# motorControllerMk3.net
KiCad netlist of a schematic drawn in EAGLE
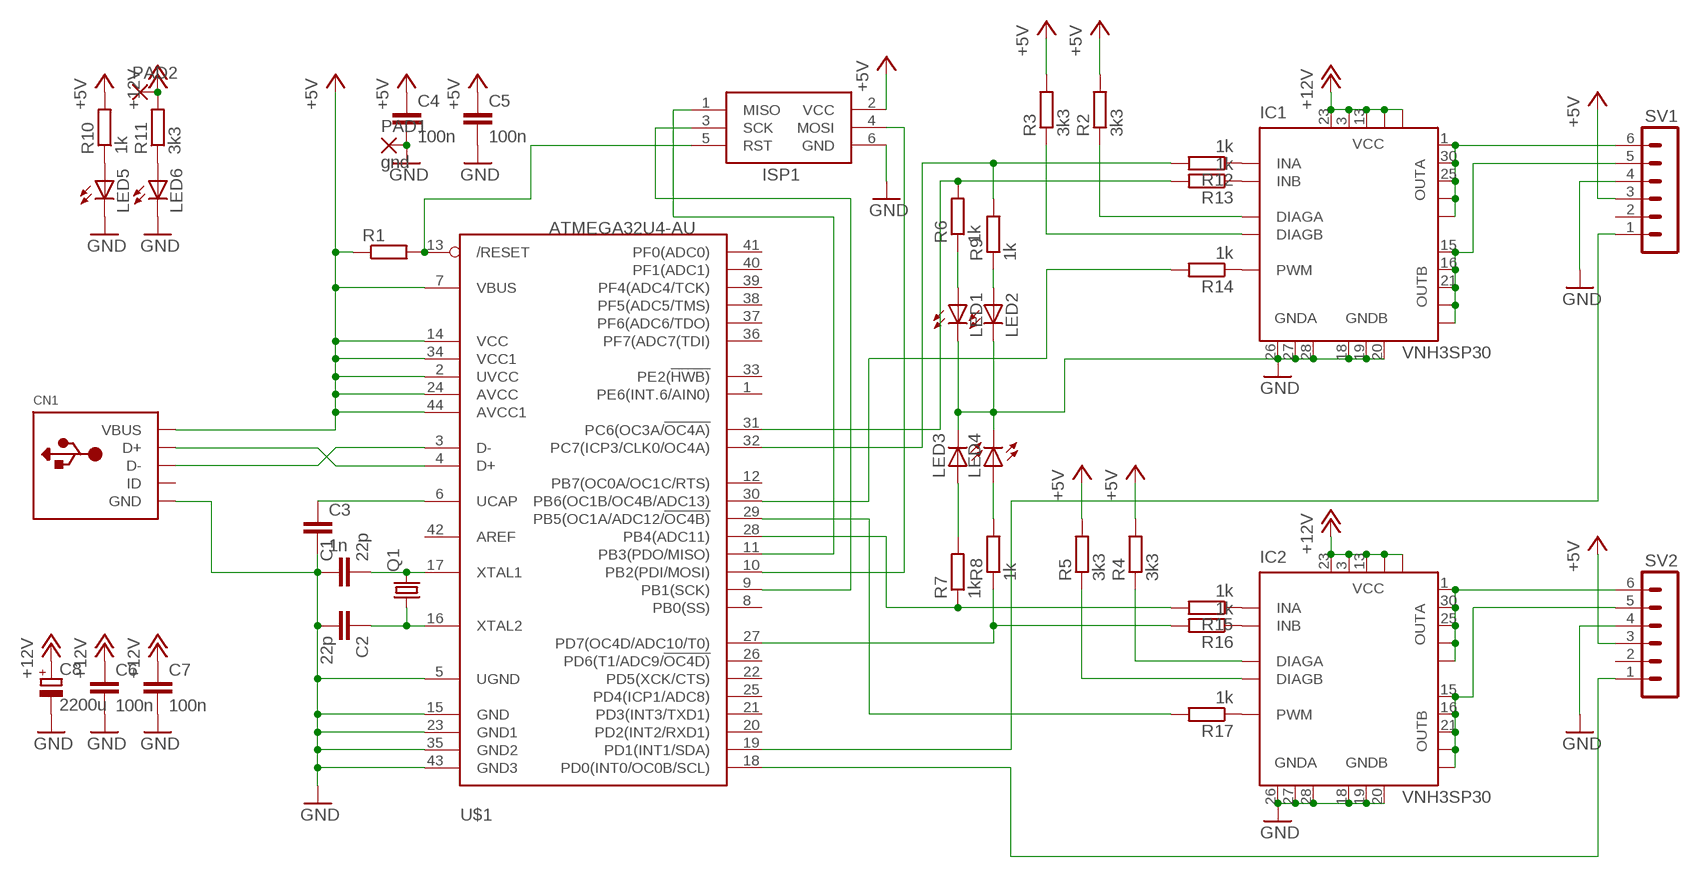
[diagram p0: schematic, sheet 1]

(export (version "E")
  (design (tool "Eeschema 10.0.6"))
  (components
    (comp (ref "C1")
      (value "22p")
      (footprint "eagle-import:C0805K")
      (libsource (lib "eagle-import") (part "C-EUC0805K"))
    )
    (comp (ref "C2")
      (value "22p")
      (footprint "eagle-import:C0805K")
      (libsource (lib "eagle-import") (part "C-EUC0805K"))
    )
    (comp (ref "C3")
      (value "1n")
      (footprint "eagle-import:C0805K")
      (libsource (lib "eagle-import") (part "C-EUC0805K"))
    )
    (comp (ref "C4")
      (value "100n")
      (footprint "eagle-import:C0805K")
      (libsource (lib "eagle-import") (part "C-EUC0805K"))
    )
    (comp (ref "C5")
      (value "100n")
      (footprint "eagle-import:C0805K")
      (libsource (lib "eagle-import") (part "C-EUC0805K"))
    )
    (comp (ref "C6")
      (value "100n")
      (footprint "eagle-import:C0805K")
      (libsource (lib "eagle-import") (part "C-EUC0805K"))
    )
    (comp (ref "C7")
      (value "100n")
      (footprint "eagle-import:C0805K")
      (libsource (lib "eagle-import") (part "C-EUC0805K"))
    )
    (comp (ref "C8")
      (value "2200u")
      (footprint "eagle-import:E5-8,5")
      (libsource (lib "eagle-import") (part "CPOL-EUE5-8.5"))
    )
    (comp (ref "CN1")
      (value "USBMINIB")
      (footprint "eagle-import:USB-MINIB")
      (libsource (lib "eagle-import") (part "USBMINIB"))
    )
    (comp (ref "IC1")
      (value "VNH3SP30")
      (footprint "eagle-import:MULTIPOWERSO-30")
      (fields (field (name "MPN") "VNH3SP30-E"))
      (libsource (lib "eagle-import") (part "VNH3SP30"))
    )
    (comp (ref "IC2")
      (value "VNH3SP30")
      (footprint "eagle-import:MULTIPOWERSO-30")
      (fields (field (name "MPN") "VNH3SP30-E"))
      (libsource (lib "eagle-import") (part "VNH3SP30"))
    )
    (comp (ref "ISP1")
      (value "AVRISP-6")
      (footprint "eagle-import:AVRISP")
      (libsource (lib "eagle-import") (part "AVRISP-6"))
    )
    (comp (ref "LED1")
      (value "LEDSML1206")
      (footprint "eagle-import:SML1206")
      (libsource (lib "eagle-import") (part "LEDSML1206"))
    )
    (comp (ref "LED2")
      (value "LEDSML1206")
      (footprint "eagle-import:SML1206")
      (libsource (lib "eagle-import") (part "LEDSML1206"))
    )
    (comp (ref "LED3")
      (value "LEDSML1206")
      (footprint "eagle-import:SML1206")
      (libsource (lib "eagle-import") (part "LEDSML1206"))
    )
    (comp (ref "LED4")
      (value "LEDSML1206")
      (footprint "eagle-import:SML1206")
      (libsource (lib "eagle-import") (part "LEDSML1206"))
    )
    (comp (ref "LED5")
      (value "LEDSML1206")
      (footprint "eagle-import:SML1206")
      (libsource (lib "eagle-import") (part "LEDSML1206"))
    )
    (comp (ref "LED6")
      (value "LEDSML1206")
      (footprint "eagle-import:SML1206")
      (libsource (lib "eagle-import") (part "LEDSML1206"))
    )
    (comp (ref "PAD1")
      (value "gnd")
      (footprint "eagle-import:3,81_1,1")
      (libsource (lib "eagle-import") (part "3,81/1,1"))
    )
    (comp (ref "PAD2")
      (value "3,81/1,1")
      (footprint "eagle-import:3,81_1,1")
      (libsource (lib "eagle-import") (part "3,81/1,1"))
    )
    (comp (ref "Q1")
      (value "CRYSTALHC49U-V")
      (footprint "eagle-import:HC49U-V")
      (libsource (lib "eagle-import") (part "CRYSTALHC49U-V"))
    )
    (comp (ref "R1")
      (value "R-EU_M0805")
      (footprint "eagle-import:M0805")
      (libsource (lib "eagle-import") (part "R-EU_M0805"))
    )
    (comp (ref "R2")
      (value "3k3")
      (footprint "eagle-import:M0805")
      (libsource (lib "eagle-import") (part "R-EU_M0805"))
    )
    (comp (ref "R3")
      (value "3k3")
      (footprint "eagle-import:M0805")
      (libsource (lib "eagle-import") (part "R-EU_M0805"))
    )
    (comp (ref "R4")
      (value "3k3")
      (footprint "eagle-import:M0805")
      (libsource (lib "eagle-import") (part "R-EU_M0805"))
    )
    (comp (ref "R5")
      (value "3k3")
      (footprint "eagle-import:M0805")
      (libsource (lib "eagle-import") (part "R-EU_M0805"))
    )
    (comp (ref "R6")
      (value "1k")
      (footprint "eagle-import:M0805")
      (libsource (lib "eagle-import") (part "R-EU_M0805"))
    )
    (comp (ref "R7")
      (value "1k")
      (footprint "eagle-import:M0805")
      (libsource (lib "eagle-import") (part "R-EU_M0805"))
    )
    (comp (ref "R8")
      (value "1k")
      (footprint "eagle-import:M0805")
      (libsource (lib "eagle-import") (part "R-EU_M0805"))
    )
    (comp (ref "R9")
      (value "1k")
      (footprint "eagle-import:M0805")
      (libsource (lib "eagle-import") (part "R-EU_M0805"))
    )
    (comp (ref "R10")
      (value "1k")
      (footprint "eagle-import:M0805")
      (libsource (lib "eagle-import") (part "R-EU_M0805"))
    )
    (comp (ref "R11")
      (value "3k3")
      (footprint "eagle-import:M0805")
      (libsource (lib "eagle-import") (part "R-EU_M0805"))
    )
    (comp (ref "R12")
      (value "1k")
      (footprint "eagle-import:M0805")
      (libsource (lib "eagle-import") (part "R-EU_M0805"))
    )
    (comp (ref "R13")
      (value "1k")
      (footprint "eagle-import:M0805")
      (libsource (lib "eagle-import") (part "R-EU_M0805"))
    )
    (comp (ref "R14")
      (value "1k")
      (footprint "eagle-import:M0805")
      (libsource (lib "eagle-import") (part "R-EU_M0805"))
    )
    (comp (ref "R15")
      (value "1k")
      (footprint "eagle-import:M0805")
      (libsource (lib "eagle-import") (part "R-EU_M0805"))
    )
    (comp (ref "R16")
      (value "1k")
      (footprint "eagle-import:M0805")
      (libsource (lib "eagle-import") (part "R-EU_M0805"))
    )
    (comp (ref "R17")
      (value "1k")
      (footprint "eagle-import:M0805")
      (libsource (lib "eagle-import") (part "R-EU_M0805"))
    )
    (comp (ref "SV1")
      (value "MA06-1")
      (footprint "eagle-import:MA06-1")
      (libsource (lib "eagle-import") (part "MA06-1"))
    )
    (comp (ref "SV2")
      (value "MA06-1")
      (footprint "eagle-import:MA06-1")
      (libsource (lib "eagle-import") (part "MA06-1"))
    )
    (comp (ref "U$1")
      (value "ATMEGA32U4-AU")
      (footprint "eagle-import:TQFP44")
      (libsource (lib "eagle-import") (part "ATMEGA32U4-AU"))
    )
  )
  (nets
    (net (code "1") (name "+5V") (class "Default")
      (node (ref "C4") (pin "1") (pinfunction "1_1") (pintype "passive"))
      (node (ref "C5") (pin "1") (pinfunction "1_1") (pintype "passive"))
      (node (ref "CN1") (pin "VBUS") (pinfunction "VBUS_VBUS") (pintype "power_in"))
      (node (ref "ISP1") (pin "2") (pinfunction "VCC_2") (pintype "power_in"))
      (node (ref "R1") (pin "1") (pinfunction "1_1") (pintype "passive"))
      (node (ref "R10") (pin "2") (pinfunction "2_2") (pintype "passive"))
      (node (ref "R2") (pin "2") (pinfunction "2_2") (pintype "passive"))
      (node (ref "R3") (pin "2") (pinfunction "2_2") (pintype "passive"))
      (node (ref "R4") (pin "2") (pinfunction "2_2") (pintype "passive"))
      (node (ref "R5") (pin "2") (pinfunction "2_2") (pintype "passive"))
      (node (ref "SV1") (pin "3") (pinfunction "3_3") (pintype "passive"))
      (node (ref "SV2") (pin "3") (pinfunction "3_3") (pintype "passive"))
      (node (ref "U$1") (pin "14") (pinfunction "VCC_14") (pintype "bidirectional"))
      (node (ref "U$1") (pin "2") (pinfunction "UVCC_2") (pintype "bidirectional"))
      (node (ref "U$1") (pin "24") (pinfunction "AVCC_24") (pintype "bidirectional"))
      (node (ref "U$1") (pin "34") (pinfunction "VCC1_34") (pintype "bidirectional"))
      (node (ref "U$1") (pin "44") (pinfunction "AVCC1_44") (pintype "bidirectional"))
      (node (ref "U$1") (pin "7") (pinfunction "VBUS_7") (pintype "bidirectional"))
    )
    (net (code "2") (name "+12V") (class "Default")
      (node (ref "C6") (pin "1") (pinfunction "1_1") (pintype "passive"))
      (node (ref "C7") (pin "1") (pinfunction "1_1") (pintype "passive"))
      (node (ref "C8") (pin "+") (pinfunction "+_+") (pintype "passive"))
      (node (ref "IC1") (pin "13") (pinfunction "VCC_13") (pintype "power_in"))
      (node (ref "IC1") (pin "23") (pinfunction "VCC_23") (pintype "power_in"))
      (node (ref "IC1") (pin "3") (pinfunction "VCC_3") (pintype "power_in"))
      (node (ref "IC1") (pin "VCC") (pinfunction "VCC_VCC") (pintype "power_in"))
      (node (ref "IC1") (pin "VCC@1") (pinfunction "VCC_VCC@1") (pintype "power_in"))
      (node (ref "IC2") (pin "13") (pinfunction "VCC_13") (pintype "power_in"))
      (node (ref "IC2") (pin "23") (pinfunction "VCC_23") (pintype "power_in"))
      (node (ref "IC2") (pin "3") (pinfunction "VCC_3") (pintype "power_in"))
      (node (ref "IC2") (pin "VCC") (pinfunction "VCC_VCC") (pintype "power_in"))
      (node (ref "IC2") (pin "VCC@1") (pinfunction "VCC_VCC@1") (pintype "power_in"))
      (node (ref "PAD2") (pin "1") (pinfunction "P_1") (pintype "passive"))
      (node (ref "R11") (pin "2") (pinfunction "2_2") (pintype "passive"))
    )
    (net (code "3") (name "GND") (class "Default")
      (node (ref "C1") (pin "1") (pinfunction "1_1") (pintype "passive"))
      (node (ref "C2") (pin "2") (pinfunction "2_2") (pintype "passive"))
      (node (ref "C3") (pin "2") (pinfunction "2_2") (pintype "passive"))
      (node (ref "C4") (pin "2") (pinfunction "2_2") (pintype "passive"))
      (node (ref "C5") (pin "2") (pinfunction "2_2") (pintype "passive"))
      (node (ref "C6") (pin "2") (pinfunction "2_2") (pintype "passive"))
      (node (ref "C7") (pin "2") (pinfunction "2_2") (pintype "passive"))
      (node (ref "C8") (pin "-") (pinfunction "-_-") (pintype "passive"))
      (node (ref "CN1") (pin "GND") (pinfunction "GND_GND") (pintype "power_in"))
      (node (ref "IC1") (pin "18") (pinfunction "GNDB_18") (pintype "power_in"))
      (node (ref "IC1") (pin "19") (pinfunction "GNDB_19") (pintype "power_in"))
      (node (ref "IC1") (pin "20") (pinfunction "GNDB_20") (pintype "power_in"))
      (node (ref "IC1") (pin "26") (pinfunction "GNDA_26") (pintype "power_in"))
      (node (ref "IC1") (pin "27") (pinfunction "GNDA_27") (pintype "power_in"))
      (node (ref "IC1") (pin "28") (pinfunction "GNDA_28") (pintype "power_in"))
      (node (ref "IC2") (pin "18") (pinfunction "GNDB_18") (pintype "power_in"))
      (node (ref "IC2") (pin "19") (pinfunction "GNDB_19") (pintype "power_in"))
      (node (ref "IC2") (pin "20") (pinfunction "GNDB_20") (pintype "power_in"))
      (node (ref "IC2") (pin "26") (pinfunction "GNDA_26") (pintype "power_in"))
      (node (ref "IC2") (pin "27") (pinfunction "GNDA_27") (pintype "power_in"))
      (node (ref "IC2") (pin "28") (pinfunction "GNDA_28") (pintype "power_in"))
      (node (ref "ISP1") (pin "6") (pinfunction "GND_6") (pintype "power_in"))
      (node (ref "LED1") (pin "C") (pinfunction "C_C") (pintype "passive"))
      (node (ref "LED2") (pin "C") (pinfunction "C_C") (pintype "passive"))
      (node (ref "LED3") (pin "C") (pinfunction "C_C") (pintype "passive"))
      (node (ref "LED4") (pin "C") (pinfunction "C_C") (pintype "passive"))
      (node (ref "LED5") (pin "C") (pinfunction "C_C") (pintype "passive"))
      (node (ref "LED6") (pin "C") (pinfunction "C_C") (pintype "passive"))
      (node (ref "PAD1") (pin "1") (pinfunction "P_1") (pintype "passive"))
      (node (ref "SV1") (pin "4") (pinfunction "4_4") (pintype "passive"))
      (node (ref "SV2") (pin "4") (pinfunction "4_4") (pintype "passive"))
      (node (ref "U$1") (pin "15") (pinfunction "GND_15") (pintype "bidirectional"))
      (node (ref "U$1") (pin "23") (pinfunction "GND1_23") (pintype "bidirectional"))
      (node (ref "U$1") (pin "35") (pinfunction "GND2_35") (pintype "bidirectional"))
      (node (ref "U$1") (pin "43") (pinfunction "GND3_43") (pintype "bidirectional"))
      (node (ref "U$1") (pin "5") (pinfunction "UGND_5") (pintype "bidirectional"))
    )
    (net (code "4") (name "Net-(IC1-DIAGA)") (class "Default")
      (node (ref "IC1") (pin "6") (pinfunction "DIAGA_6") (pintype "open_collector"))
      (node (ref "R2") (pin "1") (pinfunction "1_1") (pintype "passive"))
    )
    (net (code "5") (name "Net-(IC1-DIAGB)") (class "Default")
      (node (ref "IC1") (pin "10") (pinfunction "DIAGB_10") (pintype "open_collector"))
      (node (ref "R3") (pin "1") (pinfunction "1_1") (pintype "passive"))
    )
    (net (code "6") (name "Net-(IC1-INA)") (class "Default")
      (node (ref "IC1") (pin "5") (pinfunction "INA_5") (pintype "input"))
      (node (ref "R12") (pin "1") (pinfunction "1_1") (pintype "passive"))
    )
    (net (code "7") (name "Net-(IC1-INB)") (class "Default")
      (node (ref "IC1") (pin "11") (pinfunction "INB_11") (pintype "input"))
      (node (ref "R13") (pin "1") (pinfunction "1_1") (pintype "passive"))
    )
    (net (code "8") (name "Net-(IC1-OUTA-Pad1)") (class "Default")
      (node (ref "IC1") (pin "1") (pinfunction "OUTA_1") (pintype "output"))
      (node (ref "IC1") (pin "25") (pinfunction "OUTA_25") (pintype "passive"))
      (node (ref "IC1") (pin "30") (pinfunction "OUTA_30") (pintype "passive"))
      (node (ref "IC1") (pin "OUTA") (pinfunction "OUTA_OUTA") (pintype "passive"))
      (node (ref "IC1") (pin "OUTA@1") (pinfunction "OUTA_OUTA@1") (pintype "passive"))
      (node (ref "SV1") (pin "6") (pinfunction "6_6") (pintype "passive"))
    )
    (net (code "9") (name "Net-(IC1-OUTB-Pad15)") (class "Default")
      (node (ref "IC1") (pin "15") (pinfunction "OUTB_15") (pintype "output"))
      (node (ref "IC1") (pin "16") (pinfunction "OUTB_16") (pintype "passive"))
      (node (ref "IC1") (pin "21") (pinfunction "OUTB_21") (pintype "passive"))
      (node (ref "IC1") (pin "OUTB") (pinfunction "OUTB_OUTB") (pintype "passive"))
      (node (ref "IC1") (pin "OUTB@1") (pinfunction "OUTB_OUTB@1") (pintype "passive"))
      (node (ref "SV1") (pin "5") (pinfunction "5_5") (pintype "passive"))
    )
    (net (code "10") (name "Net-(IC1-PWM)") (class "Default")
      (node (ref "IC1") (pin "8") (pinfunction "PWM_8") (pintype "input"))
      (node (ref "R14") (pin "1") (pinfunction "1_1") (pintype "passive"))
    )
    (net (code "11") (name "Net-(IC2-DIAGA)") (class "Default")
      (node (ref "IC2") (pin "6") (pinfunction "DIAGA_6") (pintype "open_collector"))
      (node (ref "R4") (pin "1") (pinfunction "1_1") (pintype "passive"))
    )
    (net (code "12") (name "Net-(IC2-DIAGB)") (class "Default")
      (node (ref "IC2") (pin "10") (pinfunction "DIAGB_10") (pintype "open_collector"))
      (node (ref "R5") (pin "1") (pinfunction "1_1") (pintype "passive"))
    )
    (net (code "13") (name "Net-(IC2-INA)") (class "Default")
      (node (ref "IC2") (pin "5") (pinfunction "INA_5") (pintype "input"))
      (node (ref "R15") (pin "1") (pinfunction "1_1") (pintype "passive"))
    )
    (net (code "14") (name "Net-(IC2-INB)") (class "Default")
      (node (ref "IC2") (pin "11") (pinfunction "INB_11") (pintype "input"))
      (node (ref "R16") (pin "1") (pinfunction "1_1") (pintype "passive"))
    )
    (net (code "15") (name "Net-(IC2-OUTA-Pad1)") (class "Default")
      (node (ref "IC2") (pin "1") (pinfunction "OUTA_1") (pintype "output"))
      (node (ref "IC2") (pin "25") (pinfunction "OUTA_25") (pintype "passive"))
      (node (ref "IC2") (pin "30") (pinfunction "OUTA_30") (pintype "passive"))
      (node (ref "IC2") (pin "OUTA") (pinfunction "OUTA_OUTA") (pintype "passive"))
      (node (ref "IC2") (pin "OUTA@1") (pinfunction "OUTA_OUTA@1") (pintype "passive"))
      (node (ref "SV2") (pin "6") (pinfunction "6_6") (pintype "passive"))
    )
    (net (code "16") (name "Net-(IC2-OUTB-Pad15)") (class "Default")
      (node (ref "IC2") (pin "15") (pinfunction "OUTB_15") (pintype "output"))
      (node (ref "IC2") (pin "16") (pinfunction "OUTB_16") (pintype "passive"))
      (node (ref "IC2") (pin "21") (pinfunction "OUTB_21") (pintype "passive"))
      (node (ref "IC2") (pin "OUTB") (pinfunction "OUTB_OUTB") (pintype "passive"))
      (node (ref "IC2") (pin "OUTB@1") (pinfunction "OUTB_OUTB@1") (pintype "passive"))
      (node (ref "SV2") (pin "5") (pinfunction "5_5") (pintype "passive"))
    )
    (net (code "17") (name "Net-(IC2-PWM)") (class "Default")
      (node (ref "IC2") (pin "8") (pinfunction "PWM_8") (pintype "input"))
      (node (ref "R17") (pin "1") (pinfunction "1_1") (pintype "passive"))
    )
    (net (code "18") (name "Net-(ISP1-MISO)") (class "Default")
      (node (ref "ISP1") (pin "1") (pinfunction "MISO_1") (pintype "input"))
      (node (ref "U$1") (pin "11") (pinfunction "PB3(PDO/MISO)_11") (pintype "bidirectional"))
    )
    (net (code "19") (name "Net-(ISP1-MOSI)") (class "Default")
      (node (ref "ISP1") (pin "4") (pinfunction "MOSI_4") (pintype "output"))
      (node (ref "U$1") (pin "10") (pinfunction "PB2(PDI/MOSI)_10") (pintype "bidirectional"))
    )
    (net (code "20") (name "Net-(ISP1-RST)") (class "Default")
      (node (ref "ISP1") (pin "5") (pinfunction "RST_5") (pintype "output"))
      (node (ref "R1") (pin "2") (pinfunction "2_2") (pintype "passive"))
      (node (ref "U$1") (pin "13") (pinfunction "/RESET_13") (pintype "bidirectional"))
    )
    (net (code "21") (name "Net-(ISP1-SCK)") (class "Default")
      (node (ref "ISP1") (pin "3") (pinfunction "SCK_3") (pintype "output"))
      (node (ref "U$1") (pin "9") (pinfunction "PB1(SCK)_9") (pintype "bidirectional"))
    )
    (net (code "22") (name "Net-(LED1-PadA)") (class "Default")
      (node (ref "LED1") (pin "A") (pinfunction "A_A") (pintype "passive"))
      (node (ref "R6") (pin "1") (pinfunction "1_1") (pintype "passive"))
    )
    (net (code "23") (name "Net-(LED2-PadA)") (class "Default")
      (node (ref "LED2") (pin "A") (pinfunction "A_A") (pintype "passive"))
      (node (ref "R9") (pin "1") (pinfunction "1_1") (pintype "passive"))
    )
    (net (code "24") (name "Net-(LED3-PadA)") (class "Default")
      (node (ref "LED3") (pin "A") (pinfunction "A_A") (pintype "passive"))
      (node (ref "R7") (pin "2") (pinfunction "2_2") (pintype "passive"))
    )
    (net (code "25") (name "Net-(LED4-PadA)") (class "Default")
      (node (ref "LED4") (pin "A") (pinfunction "A_A") (pintype "passive"))
      (node (ref "R8") (pin "2") (pinfunction "2_2") (pintype "passive"))
    )
    (net (code "26") (name "Net-(LED5-PadA)") (class "Default")
      (node (ref "LED5") (pin "A") (pinfunction "A_A") (pintype "passive"))
      (node (ref "R10") (pin "1") (pinfunction "1_1") (pintype "passive"))
    )
    (net (code "27") (name "Net-(LED6-PadA)") (class "Default")
      (node (ref "LED6") (pin "A") (pinfunction "A_A") (pintype "passive"))
      (node (ref "R11") (pin "1") (pinfunction "1_1") (pintype "passive"))
    )
    (net (code "28") (name "Net-(U$1-D+)") (class "Default")
      (node (ref "CN1") (pin "D+") (pinfunction "D+_D+") (pintype "bidirectional"))
      (node (ref "U$1") (pin "4") (pinfunction "D+_4") (pintype "bidirectional"))
    )
    (net (code "29") (name "Net-(U$1-D-)") (class "Default")
      (node (ref "CN1") (pin "D-") (pinfunction "D-_D-") (pintype "bidirectional"))
      (node (ref "U$1") (pin "3") (pinfunction "D-_3") (pintype "bidirectional"))
    )
    (net (code "30") (name "Net-(U$1-PB4(ADC11))") (class "Default")
      (node (ref "R15") (pin "2") (pinfunction "2_2") (pintype "passive"))
      (node (ref "R7") (pin "1") (pinfunction "1_1") (pintype "passive"))
      (node (ref "U$1") (pin "28") (pinfunction "PB4(ADC11)_28") (pintype "bidirectional"))
    )
    (net (code "31") (name "Net-(U$1-PB5(OC1A{slash}ADC12{slash}~{OC4B}))") (class "Default")
      (node (ref "R17") (pin "2") (pinfunction "2_2") (pintype "passive"))
      (node (ref "U$1") (pin "29") (pinfunction "PB5(OC1A/ADC12/~{OC4B})_29") (pintype "bidirectional"))
    )
    (net (code "32") (name "Net-(U$1-PB6(OC1B{slash}OC4B{slash}ADC13))") (class "Default")
      (node (ref "R14") (pin "2") (pinfunction "2_2") (pintype "passive"))
      (node (ref "U$1") (pin "30") (pinfunction "PB6(OC1B/OC4B/ADC13)_30") (pintype "bidirectional"))
    )
    (net (code "33") (name "Net-(U$1-PC6(OC3A{slash}~{OC4A}))") (class "Default")
      (node (ref "R13") (pin "2") (pinfunction "2_2") (pintype "passive"))
      (node (ref "R6") (pin "2") (pinfunction "2_2") (pintype "passive"))
      (node (ref "U$1") (pin "31") (pinfunction "PC6(OC3A/~{OC4A})_31") (pintype "bidirectional"))
    )
    (net (code "34") (name "Net-(U$1-PC7(ICP3{slash}CLK0{slash}OC4A))") (class "Default")
      (node (ref "R12") (pin "2") (pinfunction "2_2") (pintype "passive"))
      (node (ref "R9") (pin "2") (pinfunction "2_2") (pintype "passive"))
      (node (ref "U$1") (pin "32") (pinfunction "PC7(ICP3/CLK0/OC4A)_32") (pintype "bidirectional"))
    )
    (net (code "35") (name "Net-(U$1-PD0(INT0{slash}OC0B{slash}SCL))") (class "Default")
      (node (ref "SV2") (pin "1") (pinfunction "1_1") (pintype "passive"))
      (node (ref "U$1") (pin "18") (pinfunction "PD0(INT0/OC0B/SCL)_18") (pintype "bidirectional"))
    )
    (net (code "36") (name "Net-(U$1-PD1(INT1{slash}SDA))") (class "Default")
      (node (ref "SV1") (pin "1") (pinfunction "1_1") (pintype "passive"))
      (node (ref "U$1") (pin "19") (pinfunction "PD1(INT1/SDA)_19") (pintype "bidirectional"))
    )
    (net (code "37") (name "Net-(U$1-PD7(OC4D{slash}ADC10{slash}T0))") (class "Default")
      (node (ref "R16") (pin "2") (pinfunction "2_2") (pintype "passive"))
      (node (ref "R8") (pin "1") (pinfunction "1_1") (pintype "passive"))
      (node (ref "U$1") (pin "27") (pinfunction "PD7(OC4D/ADC10/T0)_27") (pintype "bidirectional"))
    )
    (net (code "38") (name "Net-(U$1-UCAP)") (class "Default")
      (node (ref "C3") (pin "1") (pinfunction "1_1") (pintype "passive"))
      (node (ref "U$1") (pin "6") (pinfunction "UCAP_6") (pintype "bidirectional"))
    )
    (net (code "39") (name "Net-(U$1-XTAL1)") (class "Default")
      (node (ref "C1") (pin "2") (pinfunction "2_2") (pintype "passive"))
      (node (ref "Q1") (pin "2") (pinfunction "2_2") (pintype "passive"))
      (node (ref "U$1") (pin "17") (pinfunction "XTAL1_17") (pintype "bidirectional"))
    )
    (net (code "40") (name "Net-(U$1-XTAL2)") (class "Default")
      (node (ref "C2") (pin "1") (pinfunction "1_1") (pintype "passive"))
      (node (ref "Q1") (pin "1") (pinfunction "1_1") (pintype "passive"))
      (node (ref "U$1") (pin "16") (pinfunction "XTAL2_16") (pintype "bidirectional"))
    )
    (net (code "41") (name "unconnected-(CN1-PadID)") (class "Default")
      (node (ref "CN1") (pin "ID") (pinfunction "ID_ID") (pintype "bidirectional"))
    )
    (net (code "42") (name "unconnected-(SV1-Pad2)") (class "Default")
      (node (ref "SV1") (pin "2") (pinfunction "2_2") (pintype "passive"))
    )
    (net (code "43") (name "unconnected-(SV2-Pad2)") (class "Default")
      (node (ref "SV2") (pin "2") (pinfunction "2_2") (pintype "passive"))
    )
    (net (code "44") (name "unconnected-(U$1-AREF-Pad42)") (class "Default")
      (node (ref "U$1") (pin "42") (pinfunction "AREF_42") (pintype "bidirectional"))
    )
    (net (code "45") (name "unconnected-(U$1-PB0(SS)-Pad8)") (class "Default")
      (node (ref "U$1") (pin "8") (pinfunction "PB0(SS)_8") (pintype "bidirectional"))
    )
    (net (code "46") (name "unconnected-(U$1-PB7(OC0A{slash}OC1C{slash}RTS)-Pad12)") (class "Default")
      (node (ref "U$1") (pin "12") (pinfunction "PB7(OC0A/OC1C/RTS)_12") (pintype "bidirectional"))
    )
    (net (code "47") (name "unconnected-(U$1-PD2(INT2{slash}RXD1)-Pad20)") (class "Default")
      (node (ref "U$1") (pin "20") (pinfunction "PD2(INT2/RXD1)_20") (pintype "bidirectional"))
    )
    (net (code "48") (name "unconnected-(U$1-PD3(INT3{slash}TXD1)-Pad21)") (class "Default")
      (node (ref "U$1") (pin "21") (pinfunction "PD3(INT3/TXD1)_21") (pintype "bidirectional"))
    )
    (net (code "49") (name "unconnected-(U$1-PD4(ICP1{slash}ADC8)-Pad25)") (class "Default")
      (node (ref "U$1") (pin "25") (pinfunction "PD4(ICP1/ADC8)_25") (pintype "bidirectional"))
    )
    (net (code "50") (name "unconnected-(U$1-PD5(XCK{slash}CTS)-Pad22)") (class "Default")
      (node (ref "U$1") (pin "22") (pinfunction "PD5(XCK/CTS)_22") (pintype "bidirectional"))
    )
    (net (code "51") (name "unconnected-(U$1-PD6(T1{slash}ADC9{slash}~{OC4D})-Pad26)") (class "Default")
      (node (ref "U$1") (pin "26") (pinfunction "PD6(T1/ADC9/~{OC4D})_26") (pintype "bidirectional"))
    )
    (net (code "52") (name "unconnected-(U$1-PE2(~{HWB})-Pad33)") (class "Default")
      (node (ref "U$1") (pin "33") (pinfunction "PE2(~{HWB})_33") (pintype "bidirectional"))
    )
    (net (code "53") (name "unconnected-(U$1-PE6(INT.6{slash}AIN0)-Pad1)") (class "Default")
      (node (ref "U$1") (pin "1") (pinfunction "PE6(INT.6/AIN0)_1") (pintype "bidirectional"))
    )
    (net (code "54") (name "unconnected-(U$1-PF0(ADC0)-Pad41)") (class "Default")
      (node (ref "U$1") (pin "41") (pinfunction "PF0(ADC0)_41") (pintype "bidirectional"))
    )
    (net (code "55") (name "unconnected-(U$1-PF1(ADC1)-Pad40)") (class "Default")
      (node (ref "U$1") (pin "40") (pinfunction "PF1(ADC1)_40") (pintype "bidirectional"))
    )
    (net (code "56") (name "unconnected-(U$1-PF4(ADC4{slash}TCK)-Pad39)") (class "Default")
      (node (ref "U$1") (pin "39") (pinfunction "PF4(ADC4/TCK)_39") (pintype "bidirectional"))
    )
    (net (code "57") (name "unconnected-(U$1-PF5(ADC5{slash}TMS)-Pad38)") (class "Default")
      (node (ref "U$1") (pin "38") (pinfunction "PF5(ADC5/TMS)_38") (pintype "bidirectional"))
    )
    (net (code "58") (name "unconnected-(U$1-PF6(ADC6{slash}TDO)-Pad37)") (class "Default")
      (node (ref "U$1") (pin "37") (pinfunction "PF6(ADC6/TDO)_37") (pintype "bidirectional"))
    )
    (net (code "59") (name "unconnected-(U$1-PF7(ADC7(TDI)-Pad36)") (class "Default")
      (node (ref "U$1") (pin "36") (pinfunction "PF7(ADC7(TDI)_36") (pintype "bidirectional"))
    )
  )
)
